# Microcontroller.net
KiCad netlist of a schematic drawn in Altium Designer
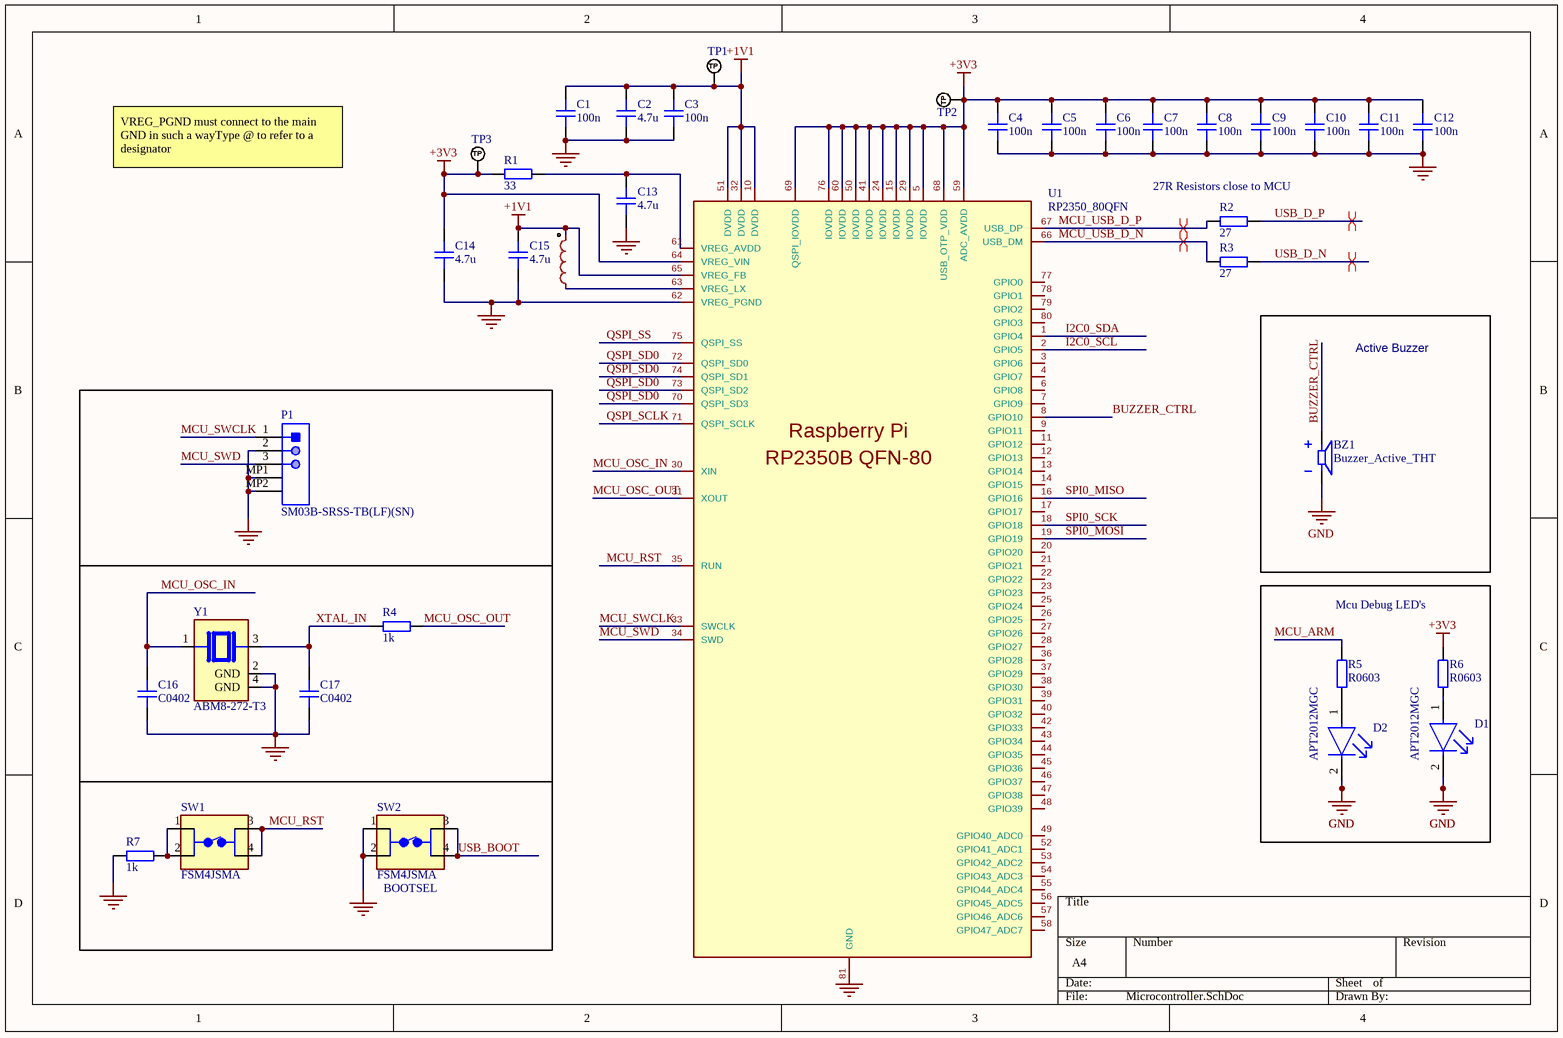
[diagram p0: Microcontroller.SchDoc]

(export (version "E")
  (design (tool "Eeschema 10.0.6"))
  (components
    (comp (ref "BZ1")
      (value "Buzzer_Active_THT")
      (footprint "Buzzer_Active_Tht")
      (libsource (lib "SchematicSchlib1") (part "Buzzer_Active_THT"))
    )
    (comp (ref "C1")
      (value "100n")
      (footprint "CAP_0402")
      (description "Capacitor SMD 0402")
      (libsource (lib "SchematicSchlib1") (part "CAP_0402"))
    )
    (comp (ref "C2")
      (value "4.7u")
      (footprint "CAP_0402")
      (description "Capacitor SMD 0402")
      (libsource (lib "SchematicSchlib1") (part "CAP_0402"))
    )
    (comp (ref "C3")
      (value "100n")
      (footprint "CAP_0402")
      (description "Capacitor SMD 0402")
      (libsource (lib "SchematicSchlib1") (part "CAP_0402"))
    )
    (comp (ref "C4")
      (value "100n")
      (footprint "CAP_0402")
      (description "Capacitor SMD 0402")
      (libsource (lib "SchematicSchlib1") (part "CAP_0402"))
    )
    (comp (ref "C5")
      (value "100n")
      (footprint "CAP_0402")
      (description "Capacitor SMD 0402")
      (libsource (lib "SchematicSchlib1") (part "CAP_0402"))
    )
    (comp (ref "C6")
      (value "100n")
      (footprint "CAP_0402")
      (description "Capacitor SMD 0402")
      (libsource (lib "SchematicSchlib1") (part "CAP_0402"))
    )
    (comp (ref "C7")
      (value "100n")
      (footprint "CAP_0402")
      (description "Capacitor SMD 0402")
      (libsource (lib "SchematicSchlib1") (part "CAP_0402"))
    )
    (comp (ref "C8")
      (value "100n")
      (footprint "CAP_0402")
      (description "Capacitor SMD 0402")
      (libsource (lib "SchematicSchlib1") (part "CAP_0402"))
    )
    (comp (ref "C9")
      (value "100n")
      (footprint "CAP_0402")
      (description "Capacitor SMD 0402")
      (libsource (lib "SchematicSchlib1") (part "CAP_0402"))
    )
    (comp (ref "C10")
      (value "100n")
      (footprint "CAP_0402")
      (description "Capacitor SMD 0402")
      (libsource (lib "SchematicSchlib1") (part "CAP_0402"))
    )
    (comp (ref "C11")
      (value "100n")
      (footprint "CAP_0402")
      (description "Capacitor SMD 0402")
      (libsource (lib "SchematicSchlib1") (part "CAP_0402"))
    )
    (comp (ref "C12")
      (value "100n")
      (footprint "CAP_0402")
      (description "Capacitor SMD 0402")
      (libsource (lib "SchematicSchlib1") (part "CAP_0402"))
    )
    (comp (ref "C13")
      (value "4.7u")
      (footprint "CAP_0402")
      (description "Capacitor SMD 0402")
      (libsource (lib "SchematicSchlib1") (part "CAP_0402"))
    )
    (comp (ref "C14")
      (value "4.7u")
      (footprint "CAP_0402")
      (description "Capacitor SMD 0402")
      (libsource (lib "SchematicSchlib1") (part "CAP_0402"))
    )
    (comp (ref "C15")
      (value "4.7u")
      (footprint "CAP_0402")
      (description "Capacitor SMD 0402")
      (libsource (lib "SchematicSchlib1") (part "CAP_0402"))
    )
    (comp (ref "C16")
      (value "C0402")
      (footprint "CAP_0402")
      (description "Capacitor SMD 0402")
      (libsource (lib "SchematicSchlib1") (part "CAP_0402"))
    )
    (comp (ref "C17")
      (value "C0402")
      (footprint "CAP_0402")
      (description "Capacitor SMD 0402")
      (libsource (lib "SchematicSchlib1") (part "CAP_0402"))
    )
    (comp (ref "D1")
      (value "APT2012MGC")
      (footprint "FP-APT2012MGC-MFG")
      (description "LED GREEN CLEAR CHIP SMD")
      (libsource (lib "Altium Content Vault") (part "ab1c01a81903e929fc6c44469aada92"))
    )
    (comp (ref "D2")
      (value "APT2012MGC")
      (footprint "FP-APT2012MGC-MFG")
      (description "LED GREEN CLEAR CHIP SMD")
      (libsource (lib "Altium Content Vault") (part "ab1c01a81903e929fc6c44469aada92"))
    )
    (comp (ref "L1")
      (value "3.3uH")
      (footprint "IND-SMD_L2.0-W1.6_AOTA-B201610S3R3-101-T")
      (fields
        (field (name "MANUFACTURER") "ABRACON")
        (field (name "MANUFACTURER PART") "AOTA-B201610S3R3-101-T")
      )
      (libsource (lib "SchematicSchlib1") (part "AOTA-B201610S3R3-101-T"))
    )
    (comp (ref "P1")
      (value "SM03B-SRSS-TB(LF)(SN)")
      (footprint "JST-SM03B-SRSS-TB_V")
      (description "Male Header, Pitch 1 mm, 1 x 3 Position, Height 2.9 mm, -25 to 85 degC, RoHS, Tape and Reel")
      (fields (field (name "MANUFACTURER") "JST"))
      (libsource (lib "Altium Content Vault") (part "CN-1P-2M-R3"))
    )
    (comp (ref "R1")
      (value "33")
      (footprint "RES_0402")
      (description "Resistor SMD 0402")
      (libsource (lib "SchematicSchlib1") (part "RES_0402"))
    )
    (comp (ref "R2")
      (value "27")
      (footprint "RES_0402")
      (description "Resistor SMD 0402")
      (libsource (lib "SchematicSchlib1") (part "RES_0402"))
    )
    (comp (ref "R3")
      (value "27")
      (footprint "RES_0402")
      (description "Resistor SMD 0402")
      (libsource (lib "SchematicSchlib1") (part "RES_0402"))
    )
    (comp (ref "R4")
      (value "1k")
      (footprint "RES_0402")
      (description "Resistor SMD 0402")
      (libsource (lib "SchematicSchlib1") (part "RES_0402"))
    )
    (comp (ref "R5")
      (value "R0603")
      (footprint "RES_0603")
      (description "Resistor SMD 0603")
      (libsource (lib "SchematicSchlib1") (part "RES_0603"))
    )
    (comp (ref "R6")
      (value "R0603")
      (footprint "RES_0603")
      (description "Resistor SMD 0603")
      (libsource (lib "SchematicSchlib1") (part "RES_0603"))
    )
    (comp (ref "R7")
      (value "1k")
      (footprint "RES_0402")
      (description "Resistor SMD 0402")
      (libsource (lib "SchematicSchlib1") (part "RES_0402"))
    )
    (comp (ref "SW1")
      (value "FSM4JSMA")
      (footprint "TE_FSM4JSMA")
      (description "Tactile Switch SPST-NO Top Actuated Surface Mount")
      (fields (field (name "MF") "TE Connectivity") (field (name "MP") "FSM-4J-SMA"))
      (libsource (lib "SchematicSchlib1") (part "FSM4JSMA"))
    )
    (comp (ref "SW2")
      (value "FSM4JSMA")
      (footprint "TE_FSM4JSMA")
      (description "Tactile Switch SPST-NO Top Actuated Surface Mount")
      (fields (field (name "MF") "TE Connectivity") (field (name "MP") "FSM-4J-SMA"))
      (libsource (lib "SchematicSchlib1") (part "FSM4JSMA"))
    )
    (comp (ref "TP1")
      (value "TEST_POINT_RND_1MM")
      (footprint "PAD_RND_1MM")
      (description "Test Point Round 1mm (NO BOM)")
      (fields (field (name "SOURCE") "Schematic-Lib-PhilsLab.SchLib"))
      (libsource (lib "Shravan Talapady") (part "TEST_POINT_RND_1MM"))
    )
    (comp (ref "TP2")
      (value "TEST_POINT_RND_1MM")
      (footprint "PAD_RND_1MM")
      (description "Test Point Round 1mm (NO BOM)")
      (fields (field (name "SOURCE") "Schematic-Lib-PhilsLab.SchLib"))
      (libsource (lib "Shravan Talapady") (part "TEST_POINT_RND_1MM"))
    )
    (comp (ref "TP3")
      (value "TEST_POINT_RND_1MM")
      (footprint "PAD_RND_1MM")
      (description "Test Point Round 1mm (NO BOM)")
      (fields (field (name "SOURCE") "Schematic-Lib-PhilsLab.SchLib"))
      (libsource (lib "Shravan Talapady") (part "TEST_POINT_RND_1MM"))
    )
    (comp (ref "U1")
      (value "RP2350_80QFN")
      (footprint "RP2350-QFN-80-1EP_10x10_P0.4mm_EP3.4x3.4mm_ThermalVias")
      (libsource (lib "SchematicSchlib1") (part "RP2350_80QFN"))
    )
    (comp (ref "Y1")
      (value "ABM8-272-T3")
      (footprint "XTAL_ABM8-272-T3")
      (description "12 MHz Â±30ppm Crystal 10pF 50 Ohms 4-SMD, No Lead")
      (fields (field (name "MF") "ABRACON"))
      (libsource (lib "SchematicSchlib1") (part "ABM8-272-T3"))
    )
  )
  (nets
    (net (code "1") (name "+1V1") (class "Default")
      (node (ref "C1") (pin "1") (pinfunction "1_1") (pintype "passive"))
      (node (ref "C15") (pin "1") (pinfunction "1_1") (pintype "passive"))
      (node (ref "C2") (pin "1") (pinfunction "1_1") (pintype "passive"))
      (node (ref "C3") (pin "1") (pinfunction "1_1") (pintype "passive"))
      (node (ref "L1") (pin "2") (pinfunction "2_2") (pintype "passive"))
      (node (ref "TP1") (pin "1") (pinfunction "TP_1") (pintype "passive"))
      (node (ref "U1") (pin "10") (pinfunction "DVDD_10") (pintype "passive"))
      (node (ref "U1") (pin "32") (pinfunction "DVDD_32") (pintype "passive"))
      (node (ref "U1") (pin "51") (pinfunction "DVDD_51") (pintype "passive"))
      (node (ref "U1") (pin "65") (pinfunction "VREG_FB_65") (pintype "passive"))
    )
    (net (code "2") (name "+3V3") (class "Default")
      (node (ref "C10") (pin "1") (pinfunction "1_1") (pintype "passive"))
      (node (ref "C11") (pin "1") (pinfunction "1_1") (pintype "passive"))
      (node (ref "C12") (pin "1") (pinfunction "1_1") (pintype "passive"))
      (node (ref "C14") (pin "1") (pinfunction "1_1") (pintype "passive"))
      (node (ref "C4") (pin "1") (pinfunction "1_1") (pintype "passive"))
      (node (ref "C5") (pin "1") (pinfunction "1_1") (pintype "passive"))
      (node (ref "C6") (pin "1") (pinfunction "1_1") (pintype "passive"))
      (node (ref "C7") (pin "1") (pinfunction "1_1") (pintype "passive"))
      (node (ref "C8") (pin "1") (pinfunction "1_1") (pintype "passive"))
      (node (ref "C9") (pin "1") (pinfunction "1_1") (pintype "passive"))
      (node (ref "R1") (pin "2") (pinfunction "2_2") (pintype "passive"))
      (node (ref "R6") (pin "2") (pinfunction "2_2") (pintype "passive"))
      (node (ref "TP2") (pin "1") (pinfunction "TP_1") (pintype "passive"))
      (node (ref "TP3") (pin "1") (pinfunction "TP_1") (pintype "passive"))
      (node (ref "U1") (pin "15") (pinfunction "IOVDD_15") (pintype "passive"))
      (node (ref "U1") (pin "24") (pinfunction "IOVDD_24") (pintype "passive"))
      (node (ref "U1") (pin "29") (pinfunction "IOVDD_29") (pintype "passive"))
      (node (ref "U1") (pin "41") (pinfunction "IOVDD_41") (pintype "passive"))
      (node (ref "U1") (pin "5") (pinfunction "IOVDD_5") (pintype "passive"))
      (node (ref "U1") (pin "50") (pinfunction "IOVDD_50") (pintype "passive"))
      (node (ref "U1") (pin "59") (pinfunction "ADC_AVDD_59") (pintype "passive"))
      (node (ref "U1") (pin "60") (pinfunction "IOVDD_60") (pintype "passive"))
      (node (ref "U1") (pin "64") (pinfunction "VREG_VIN_64") (pintype "passive"))
      (node (ref "U1") (pin "68") (pinfunction "USB_OTP_VDD_68") (pintype "passive"))
      (node (ref "U1") (pin "69") (pinfunction "QSPI_IOVDD_69") (pintype "passive"))
      (node (ref "U1") (pin "76") (pinfunction "IOVDD_76") (pintype "passive"))
    )
    (net (code "3") (name "/BUZZER_CTRL") (class "Default")
      (node (ref "BZ1") (pin "P") (pinfunction "P_P") (pintype "passive"))
      (node (ref "U1") (pin "8") (pinfunction "GPIO10_8") (pintype "passive"))
    )
    (net (code "4") (name "/I2C0_SCL") (class "Default")
      (node (ref "U1") (pin "2") (pinfunction "GPIO5_2") (pintype "passive"))
    )
    (net (code "5") (name "/I2C0_SDA") (class "Default")
      (node (ref "U1") (pin "1") (pinfunction "GPIO4_1") (pintype "passive"))
    )
    (net (code "6") (name "/MCU_ARM") (class "Default")
      (node (ref "R5") (pin "2") (pinfunction "2_2") (pintype "passive"))
    )
    (net (code "7") (name "/MCU_OSC_IN") (class "Default")
      (node (ref "C16") (pin "1") (pinfunction "1_1") (pintype "passive"))
      (node (ref "U1") (pin "30") (pinfunction "XIN_30") (pintype "passive"))
      (node (ref "Y1") (pin "1") (pinfunction "1_1") (pintype "passive"))
    )
    (net (code "8") (name "/MCU_OSC_OUT") (class "Default")
      (node (ref "R4") (pin "1") (pinfunction "1_1") (pintype "passive"))
      (node (ref "U1") (pin "31") (pinfunction "XOUT_31") (pintype "passive"))
    )
    (net (code "9") (name "/MCU_RST") (class "Default")
      (node (ref "SW1") (pin "3") (pinfunction "3_3") (pintype "passive"))
      (node (ref "SW1") (pin "4") (pinfunction "4_4") (pintype "passive"))
      (node (ref "U1") (pin "35") (pinfunction "RUN_35") (pintype "passive"))
    )
    (net (code "10") (name "/MCU_SWCLK") (class "Default")
      (node (ref "P1") (pin "1") (pinfunction "1_1") (pintype "passive"))
      (node (ref "U1") (pin "33") (pinfunction "SWCLK_33") (pintype "passive"))
    )
    (net (code "11") (name "/MCU_SWD") (class "Default")
      (node (ref "P1") (pin "3") (pinfunction "3_3") (pintype "passive"))
      (node (ref "U1") (pin "34") (pinfunction "SWD_34") (pintype "passive"))
    )
    (net (code "12") (name "/MCU_USB_D_N") (class "Default")
      (node (ref "R3") (pin "2") (pinfunction "2_2") (pintype "passive"))
      (node (ref "U1") (pin "66") (pinfunction "USB_DM_66") (pintype "passive"))
    )
    (net (code "13") (name "/MCU_USB_D_P") (class "Default")
      (node (ref "R2") (pin "2") (pinfunction "2_2") (pintype "passive"))
      (node (ref "U1") (pin "67") (pinfunction "USB_DP_67") (pintype "passive"))
    )
    (net (code "14") (name "/QSPI_SCLK") (class "Default")
      (node (ref "U1") (pin "71") (pinfunction "QSPI_SCLK_71") (pintype "passive"))
    )
    (net (code "15") (name "/QSPI_SD0") (class "Default")
      (node (ref "U1") (pin "70") (pinfunction "QSPI_SD3_70") (pintype "passive"))
      (node (ref "U1") (pin "72") (pinfunction "QSPI_SD0_72") (pintype "passive"))
      (node (ref "U1") (pin "73") (pinfunction "QSPI_SD2_73") (pintype "passive"))
      (node (ref "U1") (pin "74") (pinfunction "QSPI_SD1_74") (pintype "passive"))
    )
    (net (code "16") (name "/QSPI_SS") (class "Default")
      (node (ref "U1") (pin "75") (pinfunction "QSPI_SS_75") (pintype "passive"))
    )
    (net (code "17") (name "/SPI0_MISO") (class "Default")
      (node (ref "U1") (pin "16") (pinfunction "GPIO16_16") (pintype "passive"))
    )
    (net (code "18") (name "/SPI0_MOSI") (class "Default")
      (node (ref "U1") (pin "19") (pinfunction "GPIO19_19") (pintype "passive"))
    )
    (net (code "19") (name "/SPI0_SCK") (class "Default")
      (node (ref "U1") (pin "18") (pinfunction "GPIO18_18") (pintype "passive"))
    )
    (net (code "20") (name "/USB_BOOT") (class "Default")
      (node (ref "SW2") (pin "3") (pinfunction "3_3") (pintype "passive"))
      (node (ref "SW2") (pin "4") (pinfunction "4_4") (pintype "passive"))
    )
    (net (code "21") (name "/USB_D_N") (class "Default")
      (node (ref "R3") (pin "1") (pinfunction "1_1") (pintype "passive"))
    )
    (net (code "22") (name "/USB_D_P") (class "Default")
      (node (ref "R2") (pin "1") (pinfunction "1_1") (pintype "passive"))
    )
    (net (code "23") (name "/XTAL_IN") (class "Default")
      (node (ref "C17") (pin "1") (pinfunction "1_1") (pintype "passive"))
      (node (ref "R4") (pin "2") (pinfunction "2_2") (pintype "passive"))
      (node (ref "Y1") (pin "3") (pinfunction "3_3") (pintype "passive"))
    )
    (net (code "24") (name "GND") (class "Default")
      (node (ref "BZ1") (pin "N") (pinfunction "N_N") (pintype "passive"))
      (node (ref "C1") (pin "2") (pinfunction "2_2") (pintype "passive"))
      (node (ref "C10") (pin "2") (pinfunction "2_2") (pintype "passive"))
      (node (ref "C11") (pin "2") (pinfunction "2_2") (pintype "passive"))
      (node (ref "C12") (pin "2") (pinfunction "2_2") (pintype "passive"))
      (node (ref "C13") (pin "2") (pinfunction "2_2") (pintype "passive"))
      (node (ref "C14") (pin "2") (pinfunction "2_2") (pintype "passive"))
      (node (ref "C15") (pin "2") (pinfunction "2_2") (pintype "passive"))
      (node (ref "C16") (pin "2") (pinfunction "2_2") (pintype "passive"))
      (node (ref "C17") (pin "2") (pinfunction "2_2") (pintype "passive"))
      (node (ref "C2") (pin "2") (pinfunction "2_2") (pintype "passive"))
      (node (ref "C3") (pin "2") (pinfunction "2_2") (pintype "passive"))
      (node (ref "C4") (pin "2") (pinfunction "2_2") (pintype "passive"))
      (node (ref "C5") (pin "2") (pinfunction "2_2") (pintype "passive"))
      (node (ref "C6") (pin "2") (pinfunction "2_2") (pintype "passive"))
      (node (ref "C7") (pin "2") (pinfunction "2_2") (pintype "passive"))
      (node (ref "C8") (pin "2") (pinfunction "2_2") (pintype "passive"))
      (node (ref "C9") (pin "2") (pinfunction "2_2") (pintype "passive"))
      (node (ref "D1") (pin "2") (pinfunction "C_2") (pintype "passive"))
      (node (ref "D2") (pin "2") (pinfunction "C_2") (pintype "passive"))
      (node (ref "P1") (pin "2") (pinfunction "2_2") (pintype "passive"))
      (node (ref "P1") (pin "MP1") (pinfunction "MP1_MP1") (pintype "passive"))
      (node (ref "P1") (pin "MP2") (pinfunction "MP2_MP2") (pintype "passive"))
      (node (ref "R7") (pin "2") (pinfunction "2_2") (pintype "passive"))
      (node (ref "SW2") (pin "1") (pinfunction "1_1") (pintype "passive"))
      (node (ref "SW2") (pin "2") (pinfunction "2_2") (pintype "passive"))
      (node (ref "U1") (pin "62") (pinfunction "VREG_PGND_62") (pintype "passive"))
      (node (ref "U1") (pin "81") (pinfunction "GND_81") (pintype "passive"))
      (node (ref "Y1") (pin "2") (pinfunction "GND_2") (pintype "power_in"))
      (node (ref "Y1") (pin "4") (pinfunction "GND_4") (pintype "power_in"))
    )
    (net (code "25") (name "Net-(D1-A)") (class "Default")
      (node (ref "D1") (pin "1") (pinfunction "A_1") (pintype "passive"))
      (node (ref "R6") (pin "1") (pinfunction "1_1") (pintype "passive"))
    )
    (net (code "26") (name "Net-(D2-A)") (class "Default")
      (node (ref "D2") (pin "1") (pinfunction "A_1") (pintype "passive"))
      (node (ref "R5") (pin "1") (pinfunction "1_1") (pintype "passive"))
    )
    (net (code "27") (name "Net-(R7-Pad1)") (class "Default")
      (node (ref "R7") (pin "1") (pinfunction "1_1") (pintype "passive"))
      (node (ref "SW1") (pin "1") (pinfunction "1_1") (pintype "passive"))
      (node (ref "SW1") (pin "2") (pinfunction "2_2") (pintype "passive"))
    )
    (net (code "28") (name "Net-(U1-VREG_AVDD)") (class "Default")
      (node (ref "C13") (pin "1") (pinfunction "1_1") (pintype "passive"))
      (node (ref "R1") (pin "1") (pinfunction "1_1") (pintype "passive"))
      (node (ref "U1") (pin "61") (pinfunction "VREG_AVDD_61") (pintype "passive"))
    )
    (net (code "29") (name "Net-(U1-VREG_LX)") (class "Default")
      (node (ref "L1") (pin "1") (pinfunction "1_1") (pintype "passive"))
      (node (ref "U1") (pin "63") (pinfunction "VREG_LX_63") (pintype "passive"))
    )
    (net (code "30") (name "unconnected-(U1-GPIO0-Pad77)") (class "Default")
      (node (ref "U1") (pin "77") (pinfunction "GPIO0_77") (pintype "passive"))
    )
    (net (code "31") (name "unconnected-(U1-GPIO1-Pad78)") (class "Default")
      (node (ref "U1") (pin "78") (pinfunction "GPIO1_78") (pintype "passive"))
    )
    (net (code "32") (name "unconnected-(U1-GPIO2-Pad79)") (class "Default")
      (node (ref "U1") (pin "79") (pinfunction "GPIO2_79") (pintype "passive"))
    )
    (net (code "33") (name "unconnected-(U1-GPIO3-Pad80)") (class "Default")
      (node (ref "U1") (pin "80") (pinfunction "GPIO3_80") (pintype "passive"))
    )
    (net (code "34") (name "unconnected-(U1-GPIO6-Pad3)") (class "Default")
      (node (ref "U1") (pin "3") (pinfunction "GPIO6_3") (pintype "passive"))
    )
    (net (code "35") (name "unconnected-(U1-GPIO7-Pad4)") (class "Default")
      (node (ref "U1") (pin "4") (pinfunction "GPIO7_4") (pintype "passive"))
    )
    (net (code "36") (name "unconnected-(U1-GPIO8-Pad6)") (class "Default")
      (node (ref "U1") (pin "6") (pinfunction "GPIO8_6") (pintype "passive"))
    )
    (net (code "37") (name "unconnected-(U1-GPIO9-Pad7)") (class "Default")
      (node (ref "U1") (pin "7") (pinfunction "GPIO9_7") (pintype "passive"))
    )
    (net (code "38") (name "unconnected-(U1-GPIO11-Pad9)") (class "Default")
      (node (ref "U1") (pin "9") (pinfunction "GPIO11_9") (pintype "passive"))
    )
    (net (code "39") (name "unconnected-(U1-GPIO12-Pad11)") (class "Default")
      (node (ref "U1") (pin "11") (pinfunction "GPIO12_11") (pintype "passive"))
    )
    (net (code "40") (name "unconnected-(U1-GPIO13-Pad12)") (class "Default")
      (node (ref "U1") (pin "12") (pinfunction "GPIO13_12") (pintype "passive"))
    )
    (net (code "41") (name "unconnected-(U1-GPIO14-Pad13)") (class "Default")
      (node (ref "U1") (pin "13") (pinfunction "GPIO14_13") (pintype "passive"))
    )
    (net (code "42") (name "unconnected-(U1-GPIO15-Pad14)") (class "Default")
      (node (ref "U1") (pin "14") (pinfunction "GPIO15_14") (pintype "passive"))
    )
    (net (code "43") (name "unconnected-(U1-GPIO17-Pad17)") (class "Default")
      (node (ref "U1") (pin "17") (pinfunction "GPIO17_17") (pintype "passive"))
    )
    (net (code "44") (name "unconnected-(U1-GPIO20-Pad20)") (class "Default")
      (node (ref "U1") (pin "20") (pinfunction "GPIO20_20") (pintype "passive"))
    )
    (net (code "45") (name "unconnected-(U1-GPIO21-Pad21)") (class "Default")
      (node (ref "U1") (pin "21") (pinfunction "GPIO21_21") (pintype "passive"))
    )
    (net (code "46") (name "unconnected-(U1-GPIO22-Pad22)") (class "Default")
      (node (ref "U1") (pin "22") (pinfunction "GPIO22_22") (pintype "passive"))
    )
    (net (code "47") (name "unconnected-(U1-GPIO23-Pad23)") (class "Default")
      (node (ref "U1") (pin "23") (pinfunction "GPIO23_23") (pintype "passive"))
    )
    (net (code "48") (name "unconnected-(U1-GPIO24-Pad25)") (class "Default")
      (node (ref "U1") (pin "25") (pinfunction "GPIO24_25") (pintype "passive"))
    )
    (net (code "49") (name "unconnected-(U1-GPIO25-Pad26)") (class "Default")
      (node (ref "U1") (pin "26") (pinfunction "GPIO25_26") (pintype "passive"))
    )
    (net (code "50") (name "unconnected-(U1-GPIO26-Pad27)") (class "Default")
      (node (ref "U1") (pin "27") (pinfunction "GPIO26_27") (pintype "passive"))
    )
    (net (code "51") (name "unconnected-(U1-GPIO27-Pad28)") (class "Default")
      (node (ref "U1") (pin "28") (pinfunction "GPIO27_28") (pintype "passive"))
    )
    (net (code "52") (name "unconnected-(U1-GPIO28-Pad36)") (class "Default")
      (node (ref "U1") (pin "36") (pinfunction "GPIO28_36") (pintype "passive"))
    )
    (net (code "53") (name "unconnected-(U1-GPIO29-Pad37)") (class "Default")
      (node (ref "U1") (pin "37") (pinfunction "GPIO29_37") (pintype "passive"))
    )
    (net (code "54") (name "unconnected-(U1-GPIO30-Pad38)") (class "Default")
      (node (ref "U1") (pin "38") (pinfunction "GPIO30_38") (pintype "passive"))
    )
    (net (code "55") (name "unconnected-(U1-GPIO31-Pad39)") (class "Default")
      (node (ref "U1") (pin "39") (pinfunction "GPIO31_39") (pintype "passive"))
    )
    (net (code "56") (name "unconnected-(U1-GPIO32-Pad40)") (class "Default")
      (node (ref "U1") (pin "40") (pinfunction "GPIO32_40") (pintype "passive"))
    )
    (net (code "57") (name "unconnected-(U1-GPIO33-Pad42)") (class "Default")
      (node (ref "U1") (pin "42") (pinfunction "GPIO33_42") (pintype "passive"))
    )
    (net (code "58") (name "unconnected-(U1-GPIO34-Pad43)") (class "Default")
      (node (ref "U1") (pin "43") (pinfunction "GPIO34_43") (pintype "passive"))
    )
    (net (code "59") (name "unconnected-(U1-GPIO35-Pad44)") (class "Default")
      (node (ref "U1") (pin "44") (pinfunction "GPIO35_44") (pintype "passive"))
    )
    (net (code "60") (name "unconnected-(U1-GPIO36-Pad45)") (class "Default")
      (node (ref "U1") (pin "45") (pinfunction "GPIO36_45") (pintype "passive"))
    )
    (net (code "61") (name "unconnected-(U1-GPIO37-Pad46)") (class "Default")
      (node (ref "U1") (pin "46") (pinfunction "GPIO37_46") (pintype "passive"))
    )
    (net (code "62") (name "unconnected-(U1-GPIO38-Pad47)") (class "Default")
      (node (ref "U1") (pin "47") (pinfunction "GPIO38_47") (pintype "passive"))
    )
    (net (code "63") (name "unconnected-(U1-GPIO39-Pad48)") (class "Default")
      (node (ref "U1") (pin "48") (pinfunction "GPIO39_48") (pintype "passive"))
    )
    (net (code "64") (name "unconnected-(U1-GPIO40_ADC0-Pad49)") (class "Default")
      (node (ref "U1") (pin "49") (pinfunction "GPIO40_ADC0_49") (pintype "passive"))
    )
    (net (code "65") (name "unconnected-(U1-GPIO41_ADC1-Pad52)") (class "Default")
      (node (ref "U1") (pin "52") (pinfunction "GPIO41_ADC1_52") (pintype "passive"))
    )
    (net (code "66") (name "unconnected-(U1-GPIO42_ADC2-Pad53)") (class "Default")
      (node (ref "U1") (pin "53") (pinfunction "GPIO42_ADC2_53") (pintype "passive"))
    )
    (net (code "67") (name "unconnected-(U1-GPIO43_ADC3-Pad54)") (class "Default")
      (node (ref "U1") (pin "54") (pinfunction "GPIO43_ADC3_54") (pintype "passive"))
    )
    (net (code "68") (name "unconnected-(U1-GPIO44_ADC4-Pad55)") (class "Default")
      (node (ref "U1") (pin "55") (pinfunction "GPIO44_ADC4_55") (pintype "passive"))
    )
    (net (code "69") (name "unconnected-(U1-GPIO45_ADC5-Pad56)") (class "Default")
      (node (ref "U1") (pin "56") (pinfunction "GPIO45_ADC5_56") (pintype "passive"))
    )
    (net (code "70") (name "unconnected-(U1-GPIO46_ADC6-Pad57)") (class "Default")
      (node (ref "U1") (pin "57") (pinfunction "GPIO46_ADC6_57") (pintype "passive"))
    )
    (net (code "71") (name "unconnected-(U1-GPIO47_ADC7-Pad58)") (class "Default")
      (node (ref "U1") (pin "58") (pinfunction "GPIO47_ADC7_58") (pintype "passive"))
    )
  )
)
